# Robotic_Arm.net
KiCad netlist of a schematic drawn in EasyEDA Pro
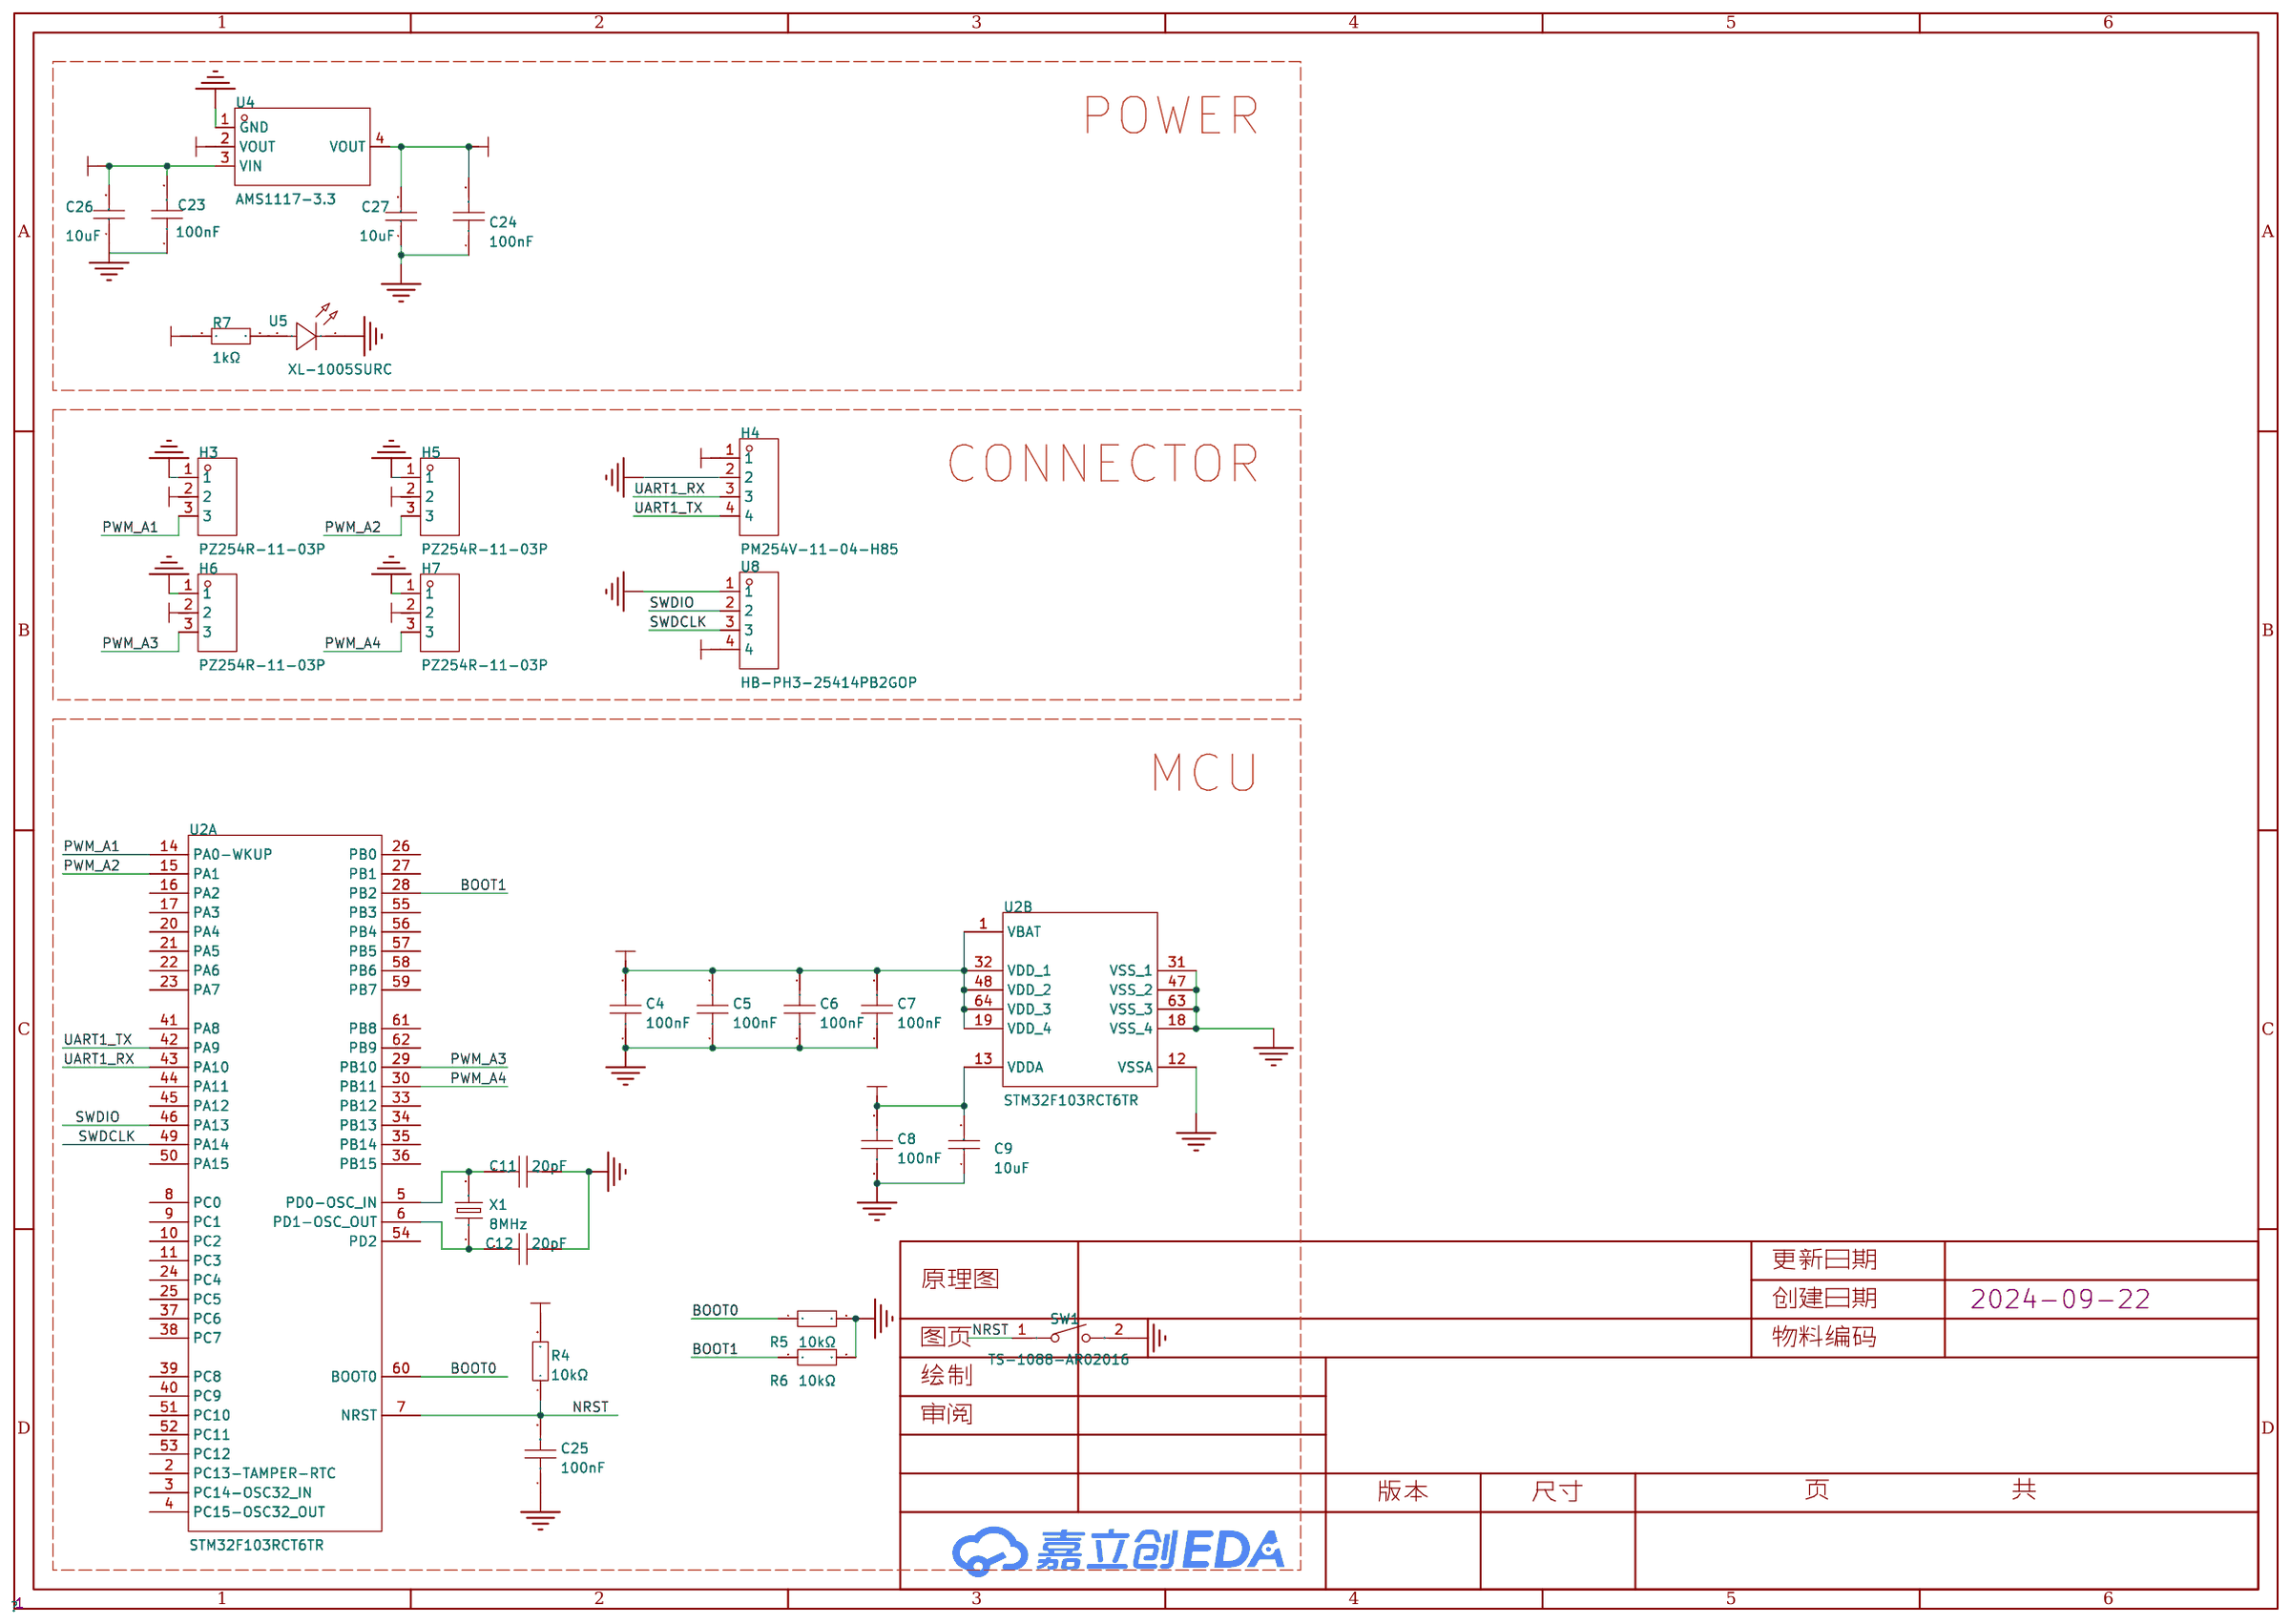
[diagram p0: schematic sheet]

(export (version "E")
  (design (tool "Eeschema 10.0.6"))
  (components
    (comp (ref "C4")
      (value "100nF")
      (footprint "easyedapro:C0402")
      (description "容值:100nF;精度:±10%;额定电压:50V;材质(温度系数):X7R;")
      (fields
        (field (name "Manufacturer Part") "GRM155R71H104KE14D")
        (field (name "Manufacturer") "muRata(村田)")
      )
      (libsource (lib "easyedapro") (part "GRM155R71H104KE14D"))
    )
    (comp (ref "C5")
      (value "100nF")
      (footprint "easyedapro:C0402")
      (description "容值:100nF;精度:±10%;额定电压:50V;材质(温度系数):X7R;")
      (fields
        (field (name "Manufacturer Part") "GRM155R71H104KE14D")
        (field (name "Manufacturer") "muRata(村田)")
      )
      (libsource (lib "easyedapro") (part "GRM155R71H104KE14D"))
    )
    (comp (ref "C6")
      (value "100nF")
      (footprint "easyedapro:C0402")
      (description "容值:100nF;精度:±10%;额定电压:50V;材质(温度系数):X7R;")
      (fields
        (field (name "Manufacturer Part") "GRM155R71H104KE14D")
        (field (name "Manufacturer") "muRata(村田)")
      )
      (libsource (lib "easyedapro") (part "GRM155R71H104KE14D"))
    )
    (comp (ref "C7")
      (value "100nF")
      (footprint "easyedapro:C0402")
      (description "容值:100nF;精度:±10%;额定电压:50V;材质(温度系数):X7R;")
      (fields
        (field (name "Manufacturer Part") "GRM155R71H104KE14D")
        (field (name "Manufacturer") "muRata(村田)")
      )
      (libsource (lib "easyedapro") (part "GRM155R71H104KE14D"))
    )
    (comp (ref "C8")
      (value "100nF")
      (footprint "easyedapro:C0402")
      (description "容值:100nF;精度:±10%;额定电压:50V;材质(温度系数):X7R;")
      (fields
        (field (name "Manufacturer Part") "GRM155R71H104KE14D")
        (field (name "Manufacturer") "muRata(村田)")
      )
      (libsource (lib "easyedapro") (part "GRM155R71H104KE14D"))
    )
    (comp (ref "C9")
      (value "10uF")
      (footprint "easyedapro:C0402")
      (description "容值:10uF;精度:±20%;额定电压:6.3V;材质(温度系数):X5R;")
      (fields
        (field (name "Manufacturer Part") "CL05A106MQ5NUNC")
        (field (name "Manufacturer") "SAMSUNG(三星)")
      )
      (libsource (lib "easyedapro") (part "CL05A106MQ5NUNC"))
    )
    (comp (ref "C11")
      (value "20pF")
      (footprint "easyedapro:C0402")
      (description "容值:20pF;精度:±5%;额定电压:50V;材质(温度系数):C0G;")
      (fields
        (field (name "Manufacturer Part") "GRM1555C1H200JA01D")
        (field (name "Manufacturer") "muRata(村田)")
      )
      (libsource (lib "easyedapro") (part "GRM1555C1H200JA01D"))
    )
    (comp (ref "C12")
      (value "20pF")
      (footprint "easyedapro:C0402")
      (description "容值:20pF;精度:±5%;额定电压:50V;材质(温度系数):C0G;")
      (fields
        (field (name "Manufacturer Part") "GRM1555C1H200JA01D")
        (field (name "Manufacturer") "muRata(村田)")
      )
      (libsource (lib "easyedapro") (part "GRM1555C1H200JA01D"))
    )
    (comp (ref "C23")
      (value "100nF")
      (footprint "easyedapro:C0402")
      (description "容值:100nF;精度:±10%;额定电压:16V;材质(温度系数):X7R;")
      (fields
        (field (name "Manufacturer Part") "CC0402KRX7R7BB104")
        (field (name "Manufacturer") "YAGEO(国巨)")
      )
      (libsource (lib "easyedapro") (part "CC0402KRX7R7BB104"))
    )
    (comp (ref "C24")
      (value "100nF")
      (footprint "easyedapro:C0402")
      (description "容值:100nF;精度:±10%;额定电压:16V;材质(温度系数):X7R;")
      (fields
        (field (name "Manufacturer Part") "CC0402KRX7R7BB104")
        (field (name "Manufacturer") "YAGEO(国巨)")
      )
      (libsource (lib "easyedapro") (part "CC0402KRX7R7BB104"))
    )
    (comp (ref "C25")
      (value "100nF")
      (footprint "easyedapro:C0402")
      (description "容值:100nF;精度:±10%;额定电压:50V;材质(温度系数):X7R;")
      (fields
        (field (name "Manufacturer Part") "GRM155R71H104KE14D")
        (field (name "Manufacturer") "muRata(村田)")
      )
      (libsource (lib "easyedapro") (part "GRM155R71H104KE14D"))
    )
    (comp (ref "C26")
      (value "10uF")
      (footprint "easyedapro:C0402")
      (description "容值:10uF;精度:±20%;额定电压:6.3V;材质(温度系数):X5R;")
      (fields
        (field (name "Manufacturer Part") "CL05A106MQ5NUNC")
        (field (name "Manufacturer") "SAMSUNG(三星)")
      )
      (libsource (lib "easyedapro") (part "CL05A106MQ5NUNC"))
    )
    (comp (ref "C27")
      (value "10uF")
      (footprint "easyedapro:C0402")
      (description "容值:10uF;精度:±20%;额定电压:6.3V;材质(温度系数):X5R;")
      (fields
        (field (name "Manufacturer Part") "CL05A106MQ5NUNC")
        (field (name "Manufacturer") "SAMSUNG(三星)")
      )
      (libsource (lib "easyedapro") (part "CL05A106MQ5NUNC"))
    )
    (comp (ref "H3")
      (value "PZ254R-11-03P")
      (footprint "easyedapro:HDR-TH_3P-P2.54-H-M-W10.4")
      (fields (field (name "Manufacturer") "XFCN(兴飞)"))
      (libsource (lib "easyedapro") (part "PZ254R-11-03P"))
    )
    (comp (ref "H4")
      (value "PM254V-11-04-H85")
      (footprint "easyedapro:HDR-TH_4P-P2.54-V-F")
      (description "插孔结构:1x4P;间距:2.54mm;行距:-;安装类型:直插;排数:单排;总孔位数:4P;塑高:-;触头材质:黄铜;触头镀层:-;")
      (fields (field (name "Manufacturer") "XFCN(兴飞)"))
      (libsource (lib "easyedapro") (part "PM254V-11-04-H85"))
    )
    (comp (ref "H5")
      (value "PZ254R-11-03P")
      (footprint "easyedapro:HDR-TH_3P-P2.54-H-M-W10.4")
      (fields (field (name "Manufacturer") "XFCN(兴飞)"))
      (libsource (lib "easyedapro") (part "PZ254R-11-03P"))
    )
    (comp (ref "H6")
      (value "PZ254R-11-03P")
      (footprint "easyedapro:HDR-TH_3P-P2.54-H-M-W10.4")
      (fields (field (name "Manufacturer") "XFCN(兴飞)"))
      (libsource (lib "easyedapro") (part "PZ254R-11-03P"))
    )
    (comp (ref "H7")
      (value "PZ254R-11-03P")
      (footprint "easyedapro:HDR-TH_3P-P2.54-H-M-W10.4")
      (fields (field (name "Manufacturer") "XFCN(兴飞)"))
      (libsource (lib "easyedapro") (part "PZ254R-11-03P"))
    )
    (comp (ref "R4")
      (value "10kΩ")
      (footprint "easyedapro:R0402")
      (description "电阻类型:厚膜电阻;阻值:10kΩ;精度:±1%;功率:62.5mW;最大工作电压:50V;温度系数:±100ppm/°C;")
      (fields (field (name "Manufacturer Part") "RC0402FR-0710KL") (field (name "Manufacturer") "YAGEO(国巨)"))
      (libsource (lib "easyedapro") (part "RC0402FR-0710KL"))
    )
    (comp (ref "R5")
      (value "10kΩ")
      (footprint "easyedapro:R0402")
      (description "电阻类型:厚膜电阻;阻值:10kΩ;精度:±1%;功率:62.5mW;最大工作电压:50V;温度系数:±100ppm/°C;")
      (fields (field (name "Manufacturer Part") "RC0402FR-0710KL") (field (name "Manufacturer") "YAGEO(国巨)"))
      (libsource (lib "easyedapro") (part "RC0402FR-0710KL"))
    )
    (comp (ref "R6")
      (value "10kΩ")
      (footprint "easyedapro:R0402")
      (description "电阻类型:厚膜电阻;阻值:10kΩ;精度:±1%;功率:62.5mW;最大工作电压:50V;温度系数:±100ppm/°C;")
      (fields (field (name "Manufacturer Part") "RC0402FR-0710KL") (field (name "Manufacturer") "YAGEO(国巨)"))
      (libsource (lib "easyedapro") (part "RC0402FR-0710KL"))
    )
    (comp (ref "R7")
      (value "1kΩ")
      (footprint "easyedapro:R0402")
      (description "电阻类型:厚膜电阻;阻值:1kΩ;精度:±1%;功率:62.5mW;最大工作电压:50V;温度系数:±100ppm/°C;")
      (fields
        (field (name "Manufacturer Part") "0402WGF1001TCE")
        (field (name "Manufacturer") "UNI-ROYAL(厚声)")
      )
      (libsource (lib "easyedapro") (part "0402WGF1001TCE"))
    )
    (comp (ref "SW1")
      (value "TS-1088-AR02016")
      (footprint "easyedapro:SW-SMD_L3.9-W3.0-P4.45")
      (fields (field (name "Manufacturer") "XUNPU(讯普)"))
      (libsource (lib "easyedapro") (part "TS-1088-AR02016"))
    )
    (comp (ref "U2")
      (value "STM32F103RCT6TR")
      (footprint "easyedapro:LQFP-64_L10.0-W10.0-P0.50-LS12.0-BL")
      (description "CPU内核:ARM-M3;程序存储容量:256KB;RAM总容量:48KB;GPIO端口数量:51;工作电压范围:2V~3.6V;CPU最大主频:72MHz;程序存储器类型:FLASH;")
      (fields (field (name "Manufacturer") "ST(意法半导体)"))
      (libsource (lib "easyedapro") (part "STM32F103RCT6TR"))
    )
    (comp (ref "U4")
      (value "AMS1117-3.3")
      (footprint "easyedapro:SOT-223-3_L6.5-W3.4-P2.30-LS7.0-BR")
      (description "输出类型:固定;最大输入电压:-;输出电压:3.3V;最大输出电流:1A;电源纹波抑制比(PSRR):72dB@(120Hz);输出极性:正极;")
      (fields (field (name "Manufacturer") "AMS"))
      (libsource (lib "easyedapro") (part "AMS1117-3.3"))
    )
    (comp (ref "U5")
      (value "XL-1005SURC")
      (footprint "easyedapro:LED0402-RD")
      (fields (field (name "Manufacturer") "XINGLIGHT(成兴光)"))
      (libsource (lib "easyedapro") (part "XL-1005SURC_C25503345"))
    )
    (comp (ref "U8")
      (value "HB-PH3-25414PB2GOP")
      (footprint "easyedapro:HDR-TH_4P-P2.54-V-M")
      (fields (field (name "Manufacturer") "HANBO(汉博)"))
      (libsource (lib "easyedapro") (part "HB-PH3-25414PB2GOP"))
    )
    (comp (ref "X1")
      (value "8MHz")
      (footprint "easyedapro:HC-49US_L11.5-W4.5-P4.88")
      (description "晶振类型:直插晶振;频率:8MHz;常温频差:±20ppm;外接负载电容:20pF;频率稳定度(全温):±20ppm;")
      (fields
        (field (name "Manufacturer Part") "49S-8.000-20-20-20/A")
        (field (name "Manufacturer") "LIMING(利明)")
      )
      (libsource (lib "easyedapro") (part "49S-8.000-20-20-20/A"))
    )
  )
  (nets
    (net (code "1") (name "/BOOT0") (class "Default")
      (node (ref "R5") (pin "1") (pinfunction "1_1") (pintype "input"))
      (node (ref "U2") (pin "60") (pinfunction "BOOT0_60") (pintype "unspecified"))
    )
    (net (code "2") (name "/BOOT1") (class "Default")
      (node (ref "R6") (pin "1") (pinfunction "1_1") (pintype "input"))
      (node (ref "U2") (pin "28") (pinfunction "PB2_28") (pintype "bidirectional"))
    )
    (net (code "3") (name "/NRST") (class "Default")
      (node (ref "C25") (pin "2") (pinfunction "2_2") (pintype "unspecified"))
      (node (ref "R4") (pin "1") (pinfunction "1_1") (pintype "input"))
      (node (ref "SW1") (pin "1") (pinfunction "1_1") (pintype "unspecified"))
      (node (ref "U2") (pin "7") (pinfunction "NRST_7") (pintype "bidirectional"))
    )
    (net (code "4") (name "/PWM_A1") (class "Default")
      (node (ref "H3") (pin "3") (pinfunction "3_3") (pintype "unspecified"))
      (node (ref "U2") (pin "14") (pinfunction "PA0-WKUP_14") (pintype "bidirectional"))
    )
    (net (code "5") (name "/PWM_A2") (class "Default")
      (node (ref "H5") (pin "3") (pinfunction "3_3") (pintype "unspecified"))
      (node (ref "U2") (pin "15") (pinfunction "PA1_15") (pintype "bidirectional"))
    )
    (net (code "6") (name "/PWM_A3") (class "Default")
      (node (ref "H6") (pin "3") (pinfunction "3_3") (pintype "unspecified"))
      (node (ref "U2") (pin "29") (pinfunction "PB10_29") (pintype "bidirectional"))
    )
    (net (code "7") (name "/PWM_A4") (class "Default")
      (node (ref "H7") (pin "3") (pinfunction "3_3") (pintype "unspecified"))
      (node (ref "U2") (pin "30") (pinfunction "PB11_30") (pintype "bidirectional"))
    )
    (net (code "8") (name "/SWDCLK") (class "Default")
      (node (ref "U2") (pin "49") (pinfunction "PA14_49") (pintype "bidirectional"))
      (node (ref "U8") (pin "3") (pinfunction "3_3") (pintype "unspecified"))
    )
    (net (code "9") (name "/SWDIO") (class "Default")
      (node (ref "U2") (pin "46") (pinfunction "PA13_46") (pintype "bidirectional"))
      (node (ref "U8") (pin "2") (pinfunction "2_2") (pintype "unspecified"))
    )
    (net (code "10") (name "/UART1_RX") (class "Default")
      (node (ref "H4") (pin "3") (pinfunction "3_3") (pintype "unspecified"))
      (node (ref "U2") (pin "43") (pinfunction "PA10_43") (pintype "bidirectional"))
    )
    (net (code "11") (name "/UART1_TX") (class "Default")
      (node (ref "H4") (pin "4") (pinfunction "4_4") (pintype "unspecified"))
      (node (ref "U2") (pin "42") (pinfunction "PA9_42") (pintype "bidirectional"))
    )
    (net (code "12") (name "3V3") (class "Default")
      (node (ref "C24") (pin "2") (pinfunction "2_2") (pintype "unspecified"))
      (node (ref "C27") (pin "2") (pinfunction "2_2") (pintype "input"))
      (node (ref "C4") (pin "2") (pinfunction "2_2") (pintype "unspecified"))
      (node (ref "C5") (pin "2") (pinfunction "2_2") (pintype "unspecified"))
      (node (ref "C6") (pin "2") (pinfunction "2_2") (pintype "unspecified"))
      (node (ref "C7") (pin "2") (pinfunction "2_2") (pintype "unspecified"))
      (node (ref "C8") (pin "2") (pinfunction "2_2") (pintype "unspecified"))
      (node (ref "C9") (pin "2") (pinfunction "2_2") (pintype "input"))
      (node (ref "R4") (pin "2") (pinfunction "2_2") (pintype "input"))
      (node (ref "R7") (pin "1") (pinfunction "1_1") (pintype "input"))
      (node (ref "U2") (pin "1") (pinfunction "VBAT_1") (pintype "unspecified"))
      (node (ref "U2") (pin "13") (pinfunction "VDDA_13") (pintype "unspecified"))
      (node (ref "U2") (pin "19") (pinfunction "VDD_4_19") (pintype "unspecified"))
      (node (ref "U2") (pin "32") (pinfunction "VDD_1_32") (pintype "unspecified"))
      (node (ref "U2") (pin "48") (pinfunction "VDD_2_48") (pintype "unspecified"))
      (node (ref "U2") (pin "64") (pinfunction "VDD_3_64") (pintype "unspecified"))
      (node (ref "U4") (pin "2") (pinfunction "VOUT_2") (pintype "unspecified"))
      (node (ref "U4") (pin "4") (pinfunction "VOUT_4") (pintype "unspecified"))
      (node (ref "U8") (pin "4") (pinfunction "4_4") (pintype "unspecified"))
    )
    (net (code "13") (name "5V") (class "Default")
      (node (ref "C23") (pin "2") (pinfunction "2_2") (pintype "unspecified"))
      (node (ref "C26") (pin "2") (pinfunction "2_2") (pintype "input"))
      (node (ref "H3") (pin "2") (pinfunction "2_2") (pintype "unspecified"))
      (node (ref "H4") (pin "1") (pinfunction "1_1") (pintype "unspecified"))
      (node (ref "H5") (pin "2") (pinfunction "2_2") (pintype "unspecified"))
      (node (ref "H6") (pin "2") (pinfunction "2_2") (pintype "unspecified"))
      (node (ref "H7") (pin "2") (pinfunction "2_2") (pintype "unspecified"))
      (node (ref "U4") (pin "3") (pinfunction "VIN_3") (pintype "unspecified"))
    )
    (net (code "14") (name "GND") (class "Default")
      (node (ref "C11") (pin "2") (pinfunction "2_2") (pintype "unspecified"))
      (node (ref "C12") (pin "2") (pinfunction "2_2") (pintype "unspecified"))
      (node (ref "C24") (pin "1") (pinfunction "1_1") (pintype "unspecified"))
      (node (ref "C25") (pin "1") (pinfunction "1_1") (pintype "unspecified"))
      (node (ref "C26") (pin "1") (pinfunction "1_1") (pintype "input"))
      (node (ref "C27") (pin "1") (pinfunction "1_1") (pintype "input"))
      (node (ref "C4") (pin "1") (pinfunction "1_1") (pintype "unspecified"))
      (node (ref "C5") (pin "1") (pinfunction "1_1") (pintype "unspecified"))
      (node (ref "C6") (pin "1") (pinfunction "1_1") (pintype "unspecified"))
      (node (ref "C7") (pin "1") (pinfunction "1_1") (pintype "unspecified"))
      (node (ref "C8") (pin "1") (pinfunction "1_1") (pintype "unspecified"))
      (node (ref "C9") (pin "1") (pinfunction "1_1") (pintype "input"))
      (node (ref "H3") (pin "1") (pinfunction "1_1") (pintype "unspecified"))
      (node (ref "H4") (pin "2") (pinfunction "2_2") (pintype "unspecified"))
      (node (ref "H5") (pin "1") (pinfunction "1_1") (pintype "unspecified"))
      (node (ref "H6") (pin "1") (pinfunction "1_1") (pintype "unspecified"))
      (node (ref "H7") (pin "1") (pinfunction "1_1") (pintype "unspecified"))
      (node (ref "R5") (pin "2") (pinfunction "2_2") (pintype "input"))
      (node (ref "R6") (pin "2") (pinfunction "2_2") (pintype "input"))
      (node (ref "SW1") (pin "2") (pinfunction "2_2") (pintype "unspecified"))
      (node (ref "U2") (pin "12") (pinfunction "VSSA_12") (pintype "unspecified"))
      (node (ref "U2") (pin "18") (pinfunction "VSS_4_18") (pintype "unspecified"))
      (node (ref "U2") (pin "31") (pinfunction "VSS_1_31") (pintype "unspecified"))
      (node (ref "U2") (pin "47") (pinfunction "VSS_2_47") (pintype "unspecified"))
      (node (ref "U2") (pin "63") (pinfunction "VSS_3_63") (pintype "unspecified"))
      (node (ref "U4") (pin "1") (pinfunction "GND_1") (pintype "unspecified"))
      (node (ref "U5") (pin "1") (pinfunction "K_1") (pintype "unspecified"))
      (node (ref "U8") (pin "1") (pinfunction "1_1") (pintype "unspecified"))
    )
    (net (code "15") (name "Net-(U2A-PD0-OSC_IN)") (class "Default")
      (node (ref "C11") (pin "1") (pinfunction "1_1") (pintype "unspecified"))
      (node (ref "U2") (pin "5") (pinfunction "PD0-OSC_IN_5") (pintype "bidirectional"))
      (node (ref "X1") (pin "2") (pinfunction "2_2") (pintype "input"))
    )
    (net (code "16") (name "Net-(U2A-PD1-OSC_OUT)") (class "Default")
      (node (ref "C12") (pin "1") (pinfunction "1_1") (pintype "unspecified"))
      (node (ref "U2") (pin "6") (pinfunction "PD1-OSC_OUT_6") (pintype "bidirectional"))
      (node (ref "X1") (pin "1") (pinfunction "1_1") (pintype "input"))
    )
    (net (code "17") (name "Net-(U5-A)") (class "Default")
      (node (ref "R7") (pin "2") (pinfunction "2_2") (pintype "input"))
      (node (ref "U5") (pin "2") (pinfunction "A_2") (pintype "unspecified"))
    )
    (net (code "18") (name "unconnected-(C23-Pad1)") (class "Default")
      (node (ref "C23") (pin "1") (pinfunction "1_1") (pintype "unspecified"))
    )
    (net (code "19") (name "unconnected-(U2A-PA2-Pad16)") (class "Default")
      (node (ref "U2") (pin "16") (pinfunction "PA2_16") (pintype "bidirectional"))
    )
    (net (code "20") (name "unconnected-(U2A-PA3-Pad17)") (class "Default")
      (node (ref "U2") (pin "17") (pinfunction "PA3_17") (pintype "bidirectional"))
    )
    (net (code "21") (name "unconnected-(U2A-PA4-Pad20)") (class "Default")
      (node (ref "U2") (pin "20") (pinfunction "PA4_20") (pintype "bidirectional"))
    )
    (net (code "22") (name "unconnected-(U2A-PA5-Pad21)") (class "Default")
      (node (ref "U2") (pin "21") (pinfunction "PA5_21") (pintype "bidirectional"))
    )
    (net (code "23") (name "unconnected-(U2A-PA6-Pad22)") (class "Default")
      (node (ref "U2") (pin "22") (pinfunction "PA6_22") (pintype "bidirectional"))
    )
    (net (code "24") (name "unconnected-(U2A-PA7-Pad23)") (class "Default")
      (node (ref "U2") (pin "23") (pinfunction "PA7_23") (pintype "bidirectional"))
    )
    (net (code "25") (name "unconnected-(U2A-PA8-Pad41)") (class "Default")
      (node (ref "U2") (pin "41") (pinfunction "PA8_41") (pintype "bidirectional"))
    )
    (net (code "26") (name "unconnected-(U2A-PA11-Pad44)") (class "Default")
      (node (ref "U2") (pin "44") (pinfunction "PA11_44") (pintype "bidirectional"))
    )
    (net (code "27") (name "unconnected-(U2A-PA12-Pad45)") (class "Default")
      (node (ref "U2") (pin "45") (pinfunction "PA12_45") (pintype "bidirectional"))
    )
    (net (code "28") (name "unconnected-(U2A-PA15-Pad50)") (class "Default")
      (node (ref "U2") (pin "50") (pinfunction "PA15_50") (pintype "bidirectional"))
    )
    (net (code "29") (name "unconnected-(U2A-PB0-Pad26)") (class "Default")
      (node (ref "U2") (pin "26") (pinfunction "PB0_26") (pintype "bidirectional"))
    )
    (net (code "30") (name "unconnected-(U2A-PB1-Pad27)") (class "Default")
      (node (ref "U2") (pin "27") (pinfunction "PB1_27") (pintype "bidirectional"))
    )
    (net (code "31") (name "unconnected-(U2A-PB3-Pad55)") (class "Default")
      (node (ref "U2") (pin "55") (pinfunction "PB3_55") (pintype "bidirectional"))
    )
    (net (code "32") (name "unconnected-(U2A-PB4-Pad56)") (class "Default")
      (node (ref "U2") (pin "56") (pinfunction "PB4_56") (pintype "bidirectional"))
    )
    (net (code "33") (name "unconnected-(U2A-PB5-Pad57)") (class "Default")
      (node (ref "U2") (pin "57") (pinfunction "PB5_57") (pintype "bidirectional"))
    )
    (net (code "34") (name "unconnected-(U2A-PB6-Pad58)") (class "Default")
      (node (ref "U2") (pin "58") (pinfunction "PB6_58") (pintype "bidirectional"))
    )
    (net (code "35") (name "unconnected-(U2A-PB7-Pad59)") (class "Default")
      (node (ref "U2") (pin "59") (pinfunction "PB7_59") (pintype "bidirectional"))
    )
    (net (code "36") (name "unconnected-(U2A-PB8-Pad61)") (class "Default")
      (node (ref "U2") (pin "61") (pinfunction "PB8_61") (pintype "bidirectional"))
    )
    (net (code "37") (name "unconnected-(U2A-PB9-Pad62)") (class "Default")
      (node (ref "U2") (pin "62") (pinfunction "PB9_62") (pintype "bidirectional"))
    )
    (net (code "38") (name "unconnected-(U2A-PB12-Pad33)") (class "Default")
      (node (ref "U2") (pin "33") (pinfunction "PB12_33") (pintype "bidirectional"))
    )
    (net (code "39") (name "unconnected-(U2A-PB13-Pad34)") (class "Default")
      (node (ref "U2") (pin "34") (pinfunction "PB13_34") (pintype "bidirectional"))
    )
    (net (code "40") (name "unconnected-(U2A-PB14-Pad35)") (class "Default")
      (node (ref "U2") (pin "35") (pinfunction "PB14_35") (pintype "bidirectional"))
    )
    (net (code "41") (name "unconnected-(U2A-PB15-Pad36)") (class "Default")
      (node (ref "U2") (pin "36") (pinfunction "PB15_36") (pintype "bidirectional"))
    )
    (net (code "42") (name "unconnected-(U2A-PC0-Pad8)") (class "Default")
      (node (ref "U2") (pin "8") (pinfunction "PC0_8") (pintype "bidirectional"))
    )
    (net (code "43") (name "unconnected-(U2A-PC1-Pad9)") (class "Default")
      (node (ref "U2") (pin "9") (pinfunction "PC1_9") (pintype "bidirectional"))
    )
    (net (code "44") (name "unconnected-(U2A-PC2-Pad10)") (class "Default")
      (node (ref "U2") (pin "10") (pinfunction "PC2_10") (pintype "bidirectional"))
    )
    (net (code "45") (name "unconnected-(U2A-PC3-Pad11)") (class "Default")
      (node (ref "U2") (pin "11") (pinfunction "PC3_11") (pintype "bidirectional"))
    )
    (net (code "46") (name "unconnected-(U2A-PC4-Pad24)") (class "Default")
      (node (ref "U2") (pin "24") (pinfunction "PC4_24") (pintype "bidirectional"))
    )
    (net (code "47") (name "unconnected-(U2A-PC5-Pad25)") (class "Default")
      (node (ref "U2") (pin "25") (pinfunction "PC5_25") (pintype "bidirectional"))
    )
    (net (code "48") (name "unconnected-(U2A-PC6-Pad37)") (class "Default")
      (node (ref "U2") (pin "37") (pinfunction "PC6_37") (pintype "bidirectional"))
    )
    (net (code "49") (name "unconnected-(U2A-PC7-Pad38)") (class "Default")
      (node (ref "U2") (pin "38") (pinfunction "PC7_38") (pintype "bidirectional"))
    )
    (net (code "50") (name "unconnected-(U2A-PC8-Pad39)") (class "Default")
      (node (ref "U2") (pin "39") (pinfunction "PC8_39") (pintype "bidirectional"))
    )
    (net (code "51") (name "unconnected-(U2A-PC9-Pad40)") (class "Default")
      (node (ref "U2") (pin "40") (pinfunction "PC9_40") (pintype "bidirectional"))
    )
    (net (code "52") (name "unconnected-(U2A-PC10-Pad51)") (class "Default")
      (node (ref "U2") (pin "51") (pinfunction "PC10_51") (pintype "bidirectional"))
    )
    (net (code "53") (name "unconnected-(U2A-PC11-Pad52)") (class "Default")
      (node (ref "U2") (pin "52") (pinfunction "PC11_52") (pintype "bidirectional"))
    )
    (net (code "54") (name "unconnected-(U2A-PC12-Pad53)") (class "Default")
      (node (ref "U2") (pin "53") (pinfunction "PC12_53") (pintype "bidirectional"))
    )
    (net (code "55") (name "unconnected-(U2A-PC13-TAMPER-RTC-Pad2)") (class "Default")
      (node (ref "U2") (pin "2") (pinfunction "PC13-TAMPER-RTC_2") (pintype "bidirectional"))
    )
    (net (code "56") (name "unconnected-(U2A-PC14-OSC32_IN-Pad3)") (class "Default")
      (node (ref "U2") (pin "3") (pinfunction "PC14-OSC32_IN_3") (pintype "bidirectional"))
    )
    (net (code "57") (name "unconnected-(U2A-PC15-OSC32_OUT-Pad4)") (class "Default")
      (node (ref "U2") (pin "4") (pinfunction "PC15-OSC32_OUT_4") (pintype "bidirectional"))
    )
    (net (code "58") (name "unconnected-(U2A-PD2-Pad54)") (class "Default")
      (node (ref "U2") (pin "54") (pinfunction "PD2_54") (pintype "bidirectional"))
    )
  )
)
